# balise.net
KiCad netlist of a schematic drawn in EAGLE
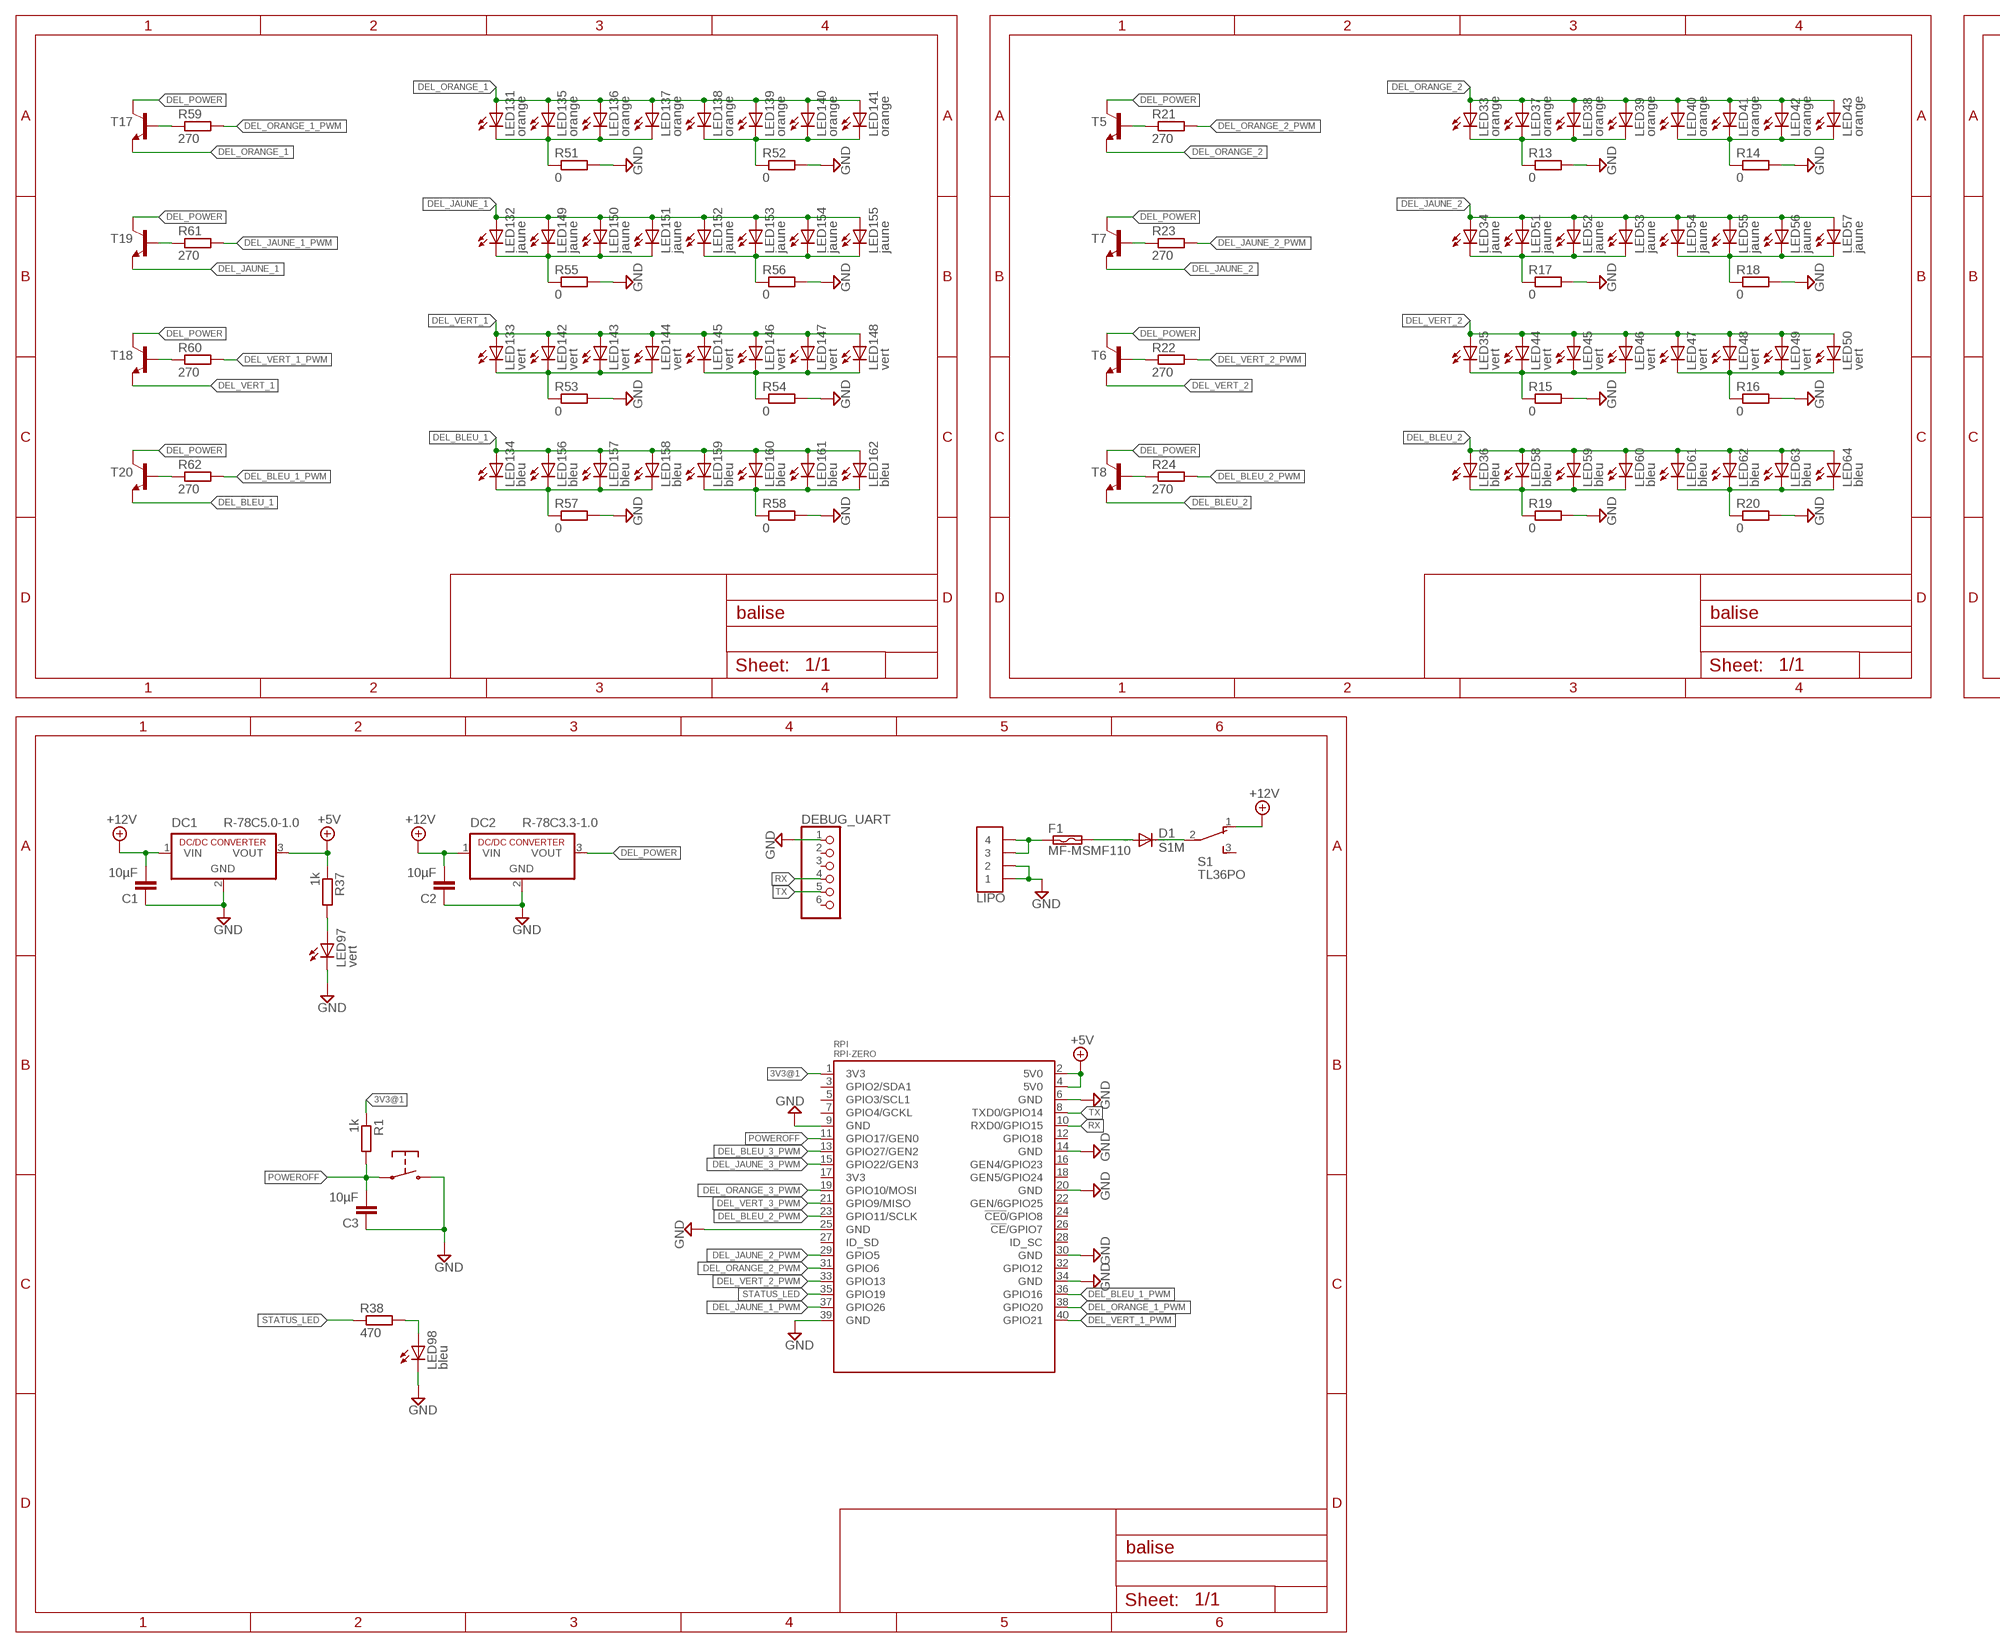
[diagram p0: schematic, sheet 1, part 1 of 2]
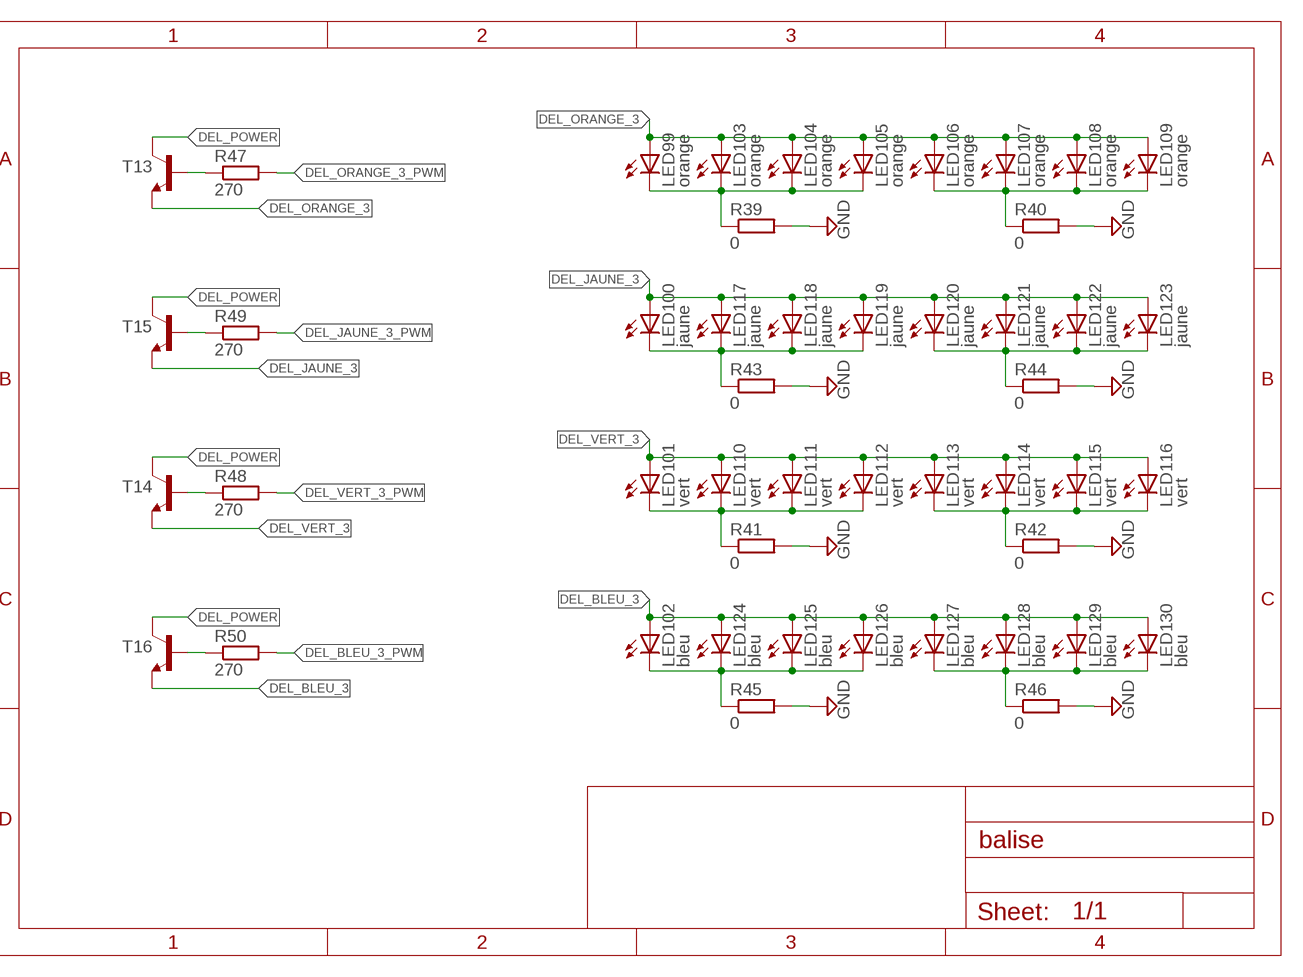
[diagram p1: schematic, sheet 1, part 2 of 2]

(export (version "E")
  (design (tool "Eeschema 10.0.6"))
  (components
    (comp (ref "C1")
      (value "10µF")
      (footprint "eagle-import:C0805")
      (libsource (lib "eagle-import") (part "C-EUC0805"))
    )
    (comp (ref "C2")
      (value "10µF")
      (footprint "eagle-import:C0805")
      (libsource (lib "eagle-import") (part "C-EUC0805"))
    )
    (comp (ref "C3")
      (value "10µF")
      (footprint "eagle-import:C0805")
      (libsource (lib "eagle-import") (part "C-EUC0805"))
    )
    (comp (ref "D1")
      (value "S1M")
      (footprint "eagle-import:SMA")
      (libsource (lib "eagle-import") (part "S1M"))
    )
    (comp (ref "DC1")
      (value "R-78C5.0-1.0")
      (footprint "eagle-import:SIP3")
      (libsource (lib "eagle-import") (part "R-78C-1.05.0"))
    )
    (comp (ref "DC2")
      (value "R-78C3.3-1.0")
      (footprint "eagle-import:SIP3")
      (libsource (lib "eagle-import") (part "R-78C-1.03.3"))
    )
    (comp (ref "DEBUG_UART")
      (value "PINHD-1X6")
      (footprint "eagle-import:1X06")
      (libsource (lib "eagle-import") (part "PINHD-1X6"))
    )
    (comp (ref "F1")
      (value "MF-MSMF110")
      (footprint "eagle-import:MF-MSMF110")
      (libsource (lib "eagle-import") (part "MF-MSMF110"))
    )
    (comp (ref "LED33")
      (value "orange")
      (footprint "eagle-import:LED5MM")
      (libsource (lib "eagle-import") (part "LED5MM"))
    )
    (comp (ref "LED34")
      (value "jaune")
      (footprint "eagle-import:LED5MM")
      (libsource (lib "eagle-import") (part "LED5MM"))
    )
    (comp (ref "LED35")
      (value "vert")
      (footprint "eagle-import:LED5MM")
      (libsource (lib "eagle-import") (part "LED5MM"))
    )
    (comp (ref "LED36")
      (value "bleu")
      (footprint "eagle-import:LED5MM")
      (libsource (lib "eagle-import") (part "LED5MM"))
    )
    (comp (ref "LED37")
      (value "orange")
      (footprint "eagle-import:LED5MM")
      (libsource (lib "eagle-import") (part "LED5MM"))
    )
    (comp (ref "LED38")
      (value "orange")
      (footprint "eagle-import:LED5MM")
      (libsource (lib "eagle-import") (part "LED5MM"))
    )
    (comp (ref "LED39")
      (value "orange")
      (footprint "eagle-import:LED5MM")
      (libsource (lib "eagle-import") (part "LED5MM"))
    )
    (comp (ref "LED40")
      (value "orange")
      (footprint "eagle-import:LED5MM")
      (libsource (lib "eagle-import") (part "LED5MM"))
    )
    (comp (ref "LED41")
      (value "orange")
      (footprint "eagle-import:LED5MM")
      (libsource (lib "eagle-import") (part "LED5MM"))
    )
    (comp (ref "LED42")
      (value "orange")
      (footprint "eagle-import:LED5MM")
      (libsource (lib "eagle-import") (part "LED5MM"))
    )
    (comp (ref "LED43")
      (value "orange")
      (footprint "eagle-import:LED5MM")
      (libsource (lib "eagle-import") (part "LED5MM"))
    )
    (comp (ref "LED44")
      (value "vert")
      (footprint "eagle-import:LED5MM")
      (libsource (lib "eagle-import") (part "LED5MM"))
    )
    (comp (ref "LED45")
      (value "vert")
      (footprint "eagle-import:LED5MM")
      (libsource (lib "eagle-import") (part "LED5MM"))
    )
    (comp (ref "LED46")
      (value "vert")
      (footprint "eagle-import:LED5MM")
      (libsource (lib "eagle-import") (part "LED5MM"))
    )
    (comp (ref "LED47")
      (value "vert")
      (footprint "eagle-import:LED5MM")
      (libsource (lib "eagle-import") (part "LED5MM"))
    )
    (comp (ref "LED48")
      (value "vert")
      (footprint "eagle-import:LED5MM")
      (libsource (lib "eagle-import") (part "LED5MM"))
    )
    (comp (ref "LED49")
      (value "vert")
      (footprint "eagle-import:LED5MM")
      (libsource (lib "eagle-import") (part "LED5MM"))
    )
    (comp (ref "LED50")
      (value "vert")
      (footprint "eagle-import:LED5MM")
      (libsource (lib "eagle-import") (part "LED5MM"))
    )
    (comp (ref "LED51")
      (value "jaune")
      (footprint "eagle-import:LED5MM")
      (libsource (lib "eagle-import") (part "LED5MM"))
    )
    (comp (ref "LED52")
      (value "jaune")
      (footprint "eagle-import:LED5MM")
      (libsource (lib "eagle-import") (part "LED5MM"))
    )
    (comp (ref "LED53")
      (value "jaune")
      (footprint "eagle-import:LED5MM")
      (libsource (lib "eagle-import") (part "LED5MM"))
    )
    (comp (ref "LED54")
      (value "jaune")
      (footprint "eagle-import:LED5MM")
      (libsource (lib "eagle-import") (part "LED5MM"))
    )
    (comp (ref "LED55")
      (value "jaune")
      (footprint "eagle-import:LED5MM")
      (libsource (lib "eagle-import") (part "LED5MM"))
    )
    (comp (ref "LED56")
      (value "jaune")
      (footprint "eagle-import:LED5MM")
      (libsource (lib "eagle-import") (part "LED5MM"))
    )
    (comp (ref "LED57")
      (value "jaune")
      (footprint "eagle-import:LED5MM")
      (libsource (lib "eagle-import") (part "LED5MM"))
    )
    (comp (ref "LED58")
      (value "bleu")
      (footprint "eagle-import:LED5MM")
      (libsource (lib "eagle-import") (part "LED5MM"))
    )
    (comp (ref "LED59")
      (value "bleu")
      (footprint "eagle-import:LED5MM")
      (libsource (lib "eagle-import") (part "LED5MM"))
    )
    (comp (ref "LED60")
      (value "bleu")
      (footprint "eagle-import:LED5MM")
      (libsource (lib "eagle-import") (part "LED5MM"))
    )
    (comp (ref "LED61")
      (value "bleu")
      (footprint "eagle-import:LED5MM")
      (libsource (lib "eagle-import") (part "LED5MM"))
    )
    (comp (ref "LED62")
      (value "bleu")
      (footprint "eagle-import:LED5MM")
      (libsource (lib "eagle-import") (part "LED5MM"))
    )
    (comp (ref "LED63")
      (value "bleu")
      (footprint "eagle-import:LED5MM")
      (libsource (lib "eagle-import") (part "LED5MM"))
    )
    (comp (ref "LED64")
      (value "bleu")
      (footprint "eagle-import:LED5MM")
      (libsource (lib "eagle-import") (part "LED5MM"))
    )
    (comp (ref "LED97")
      (value "vert")
      (footprint "eagle-import:LED5MM")
      (libsource (lib "eagle-import") (part "LED5MM"))
    )
    (comp (ref "LED98")
      (value "bleu")
      (footprint "eagle-import:LED5MM")
      (libsource (lib "eagle-import") (part "LED5MM"))
    )
    (comp (ref "LED99")
      (value "orange")
      (footprint "eagle-import:LED5MM")
      (libsource (lib "eagle-import") (part "LED5MM"))
    )
    (comp (ref "LED100")
      (value "jaune")
      (footprint "eagle-import:LED5MM")
      (libsource (lib "eagle-import") (part "LED5MM"))
    )
    (comp (ref "LED101")
      (value "vert")
      (footprint "eagle-import:LED5MM")
      (libsource (lib "eagle-import") (part "LED5MM"))
    )
    (comp (ref "LED102")
      (value "bleu")
      (footprint "eagle-import:LED5MM")
      (libsource (lib "eagle-import") (part "LED5MM"))
    )
    (comp (ref "LED103")
      (value "orange")
      (footprint "eagle-import:LED5MM")
      (libsource (lib "eagle-import") (part "LED5MM"))
    )
    (comp (ref "LED104")
      (value "orange")
      (footprint "eagle-import:LED5MM")
      (libsource (lib "eagle-import") (part "LED5MM"))
    )
    (comp (ref "LED105")
      (value "orange")
      (footprint "eagle-import:LED5MM")
      (libsource (lib "eagle-import") (part "LED5MM"))
    )
    (comp (ref "LED106")
      (value "orange")
      (footprint "eagle-import:LED5MM")
      (libsource (lib "eagle-import") (part "LED5MM"))
    )
    (comp (ref "LED107")
      (value "orange")
      (footprint "eagle-import:LED5MM")
      (libsource (lib "eagle-import") (part "LED5MM"))
    )
    (comp (ref "LED108")
      (value "orange")
      (footprint "eagle-import:LED5MM")
      (libsource (lib "eagle-import") (part "LED5MM"))
    )
    (comp (ref "LED109")
      (value "orange")
      (footprint "eagle-import:LED5MM")
      (libsource (lib "eagle-import") (part "LED5MM"))
    )
    (comp (ref "LED110")
      (value "vert")
      (footprint "eagle-import:LED5MM")
      (libsource (lib "eagle-import") (part "LED5MM"))
    )
    (comp (ref "LED111")
      (value "vert")
      (footprint "eagle-import:LED5MM")
      (libsource (lib "eagle-import") (part "LED5MM"))
    )
    (comp (ref "LED112")
      (value "vert")
      (footprint "eagle-import:LED5MM")
      (libsource (lib "eagle-import") (part "LED5MM"))
    )
    (comp (ref "LED113")
      (value "vert")
      (footprint "eagle-import:LED5MM")
      (libsource (lib "eagle-import") (part "LED5MM"))
    )
    (comp (ref "LED114")
      (value "vert")
      (footprint "eagle-import:LED5MM")
      (libsource (lib "eagle-import") (part "LED5MM"))
    )
    (comp (ref "LED115")
      (value "vert")
      (footprint "eagle-import:LED5MM")
      (libsource (lib "eagle-import") (part "LED5MM"))
    )
    (comp (ref "LED116")
      (value "vert")
      (footprint "eagle-import:LED5MM")
      (libsource (lib "eagle-import") (part "LED5MM"))
    )
    (comp (ref "LED117")
      (value "jaune")
      (footprint "eagle-import:LED5MM")
      (libsource (lib "eagle-import") (part "LED5MM"))
    )
    (comp (ref "LED118")
      (value "jaune")
      (footprint "eagle-import:LED5MM")
      (libsource (lib "eagle-import") (part "LED5MM"))
    )
    (comp (ref "LED119")
      (value "jaune")
      (footprint "eagle-import:LED5MM")
      (libsource (lib "eagle-import") (part "LED5MM"))
    )
    (comp (ref "LED120")
      (value "jaune")
      (footprint "eagle-import:LED5MM")
      (libsource (lib "eagle-import") (part "LED5MM"))
    )
    (comp (ref "LED121")
      (value "jaune")
      (footprint "eagle-import:LED5MM")
      (libsource (lib "eagle-import") (part "LED5MM"))
    )
    (comp (ref "LED122")
      (value "jaune")
      (footprint "eagle-import:LED5MM")
      (libsource (lib "eagle-import") (part "LED5MM"))
    )
    (comp (ref "LED123")
      (value "jaune")
      (footprint "eagle-import:LED5MM")
      (libsource (lib "eagle-import") (part "LED5MM"))
    )
    (comp (ref "LED124")
      (value "bleu")
      (footprint "eagle-import:LED5MM")
      (libsource (lib "eagle-import") (part "LED5MM"))
    )
    (comp (ref "LED125")
      (value "bleu")
      (footprint "eagle-import:LED5MM")
      (libsource (lib "eagle-import") (part "LED5MM"))
    )
    (comp (ref "LED126")
      (value "bleu")
      (footprint "eagle-import:LED5MM")
      (libsource (lib "eagle-import") (part "LED5MM"))
    )
    (comp (ref "LED127")
      (value "bleu")
      (footprint "eagle-import:LED5MM")
      (libsource (lib "eagle-import") (part "LED5MM"))
    )
    (comp (ref "LED128")
      (value "bleu")
      (footprint "eagle-import:LED5MM")
      (libsource (lib "eagle-import") (part "LED5MM"))
    )
    (comp (ref "LED129")
      (value "bleu")
      (footprint "eagle-import:LED5MM")
      (libsource (lib "eagle-import") (part "LED5MM"))
    )
    (comp (ref "LED130")
      (value "bleu")
      (footprint "eagle-import:LED5MM")
      (libsource (lib "eagle-import") (part "LED5MM"))
    )
    (comp (ref "LED131")
      (value "orange")
      (footprint "eagle-import:LED5MM")
      (libsource (lib "eagle-import") (part "LED5MM"))
    )
    (comp (ref "LED132")
      (value "jaune")
      (footprint "eagle-import:LED5MM")
      (libsource (lib "eagle-import") (part "LED5MM"))
    )
    (comp (ref "LED133")
      (value "vert")
      (footprint "eagle-import:LED5MM")
      (libsource (lib "eagle-import") (part "LED5MM"))
    )
    (comp (ref "LED134")
      (value "bleu")
      (footprint "eagle-import:LED5MM")
      (libsource (lib "eagle-import") (part "LED5MM"))
    )
    (comp (ref "LED135")
      (value "orange")
      (footprint "eagle-import:LED5MM")
      (libsource (lib "eagle-import") (part "LED5MM"))
    )
    (comp (ref "LED136")
      (value "orange")
      (footprint "eagle-import:LED5MM")
      (libsource (lib "eagle-import") (part "LED5MM"))
    )
    (comp (ref "LED137")
      (value "orange")
      (footprint "eagle-import:LED5MM")
      (libsource (lib "eagle-import") (part "LED5MM"))
    )
    (comp (ref "LED138")
      (value "orange")
      (footprint "eagle-import:LED5MM")
      (libsource (lib "eagle-import") (part "LED5MM"))
    )
    (comp (ref "LED139")
      (value "orange")
      (footprint "eagle-import:LED5MM")
      (libsource (lib "eagle-import") (part "LED5MM"))
    )
    (comp (ref "LED140")
      (value "orange")
      (footprint "eagle-import:LED5MM")
      (libsource (lib "eagle-import") (part "LED5MM"))
    )
    (comp (ref "LED141")
      (value "orange")
      (footprint "eagle-import:LED5MM")
      (libsource (lib "eagle-import") (part "LED5MM"))
    )
    (comp (ref "LED142")
      (value "vert")
      (footprint "eagle-import:LED5MM")
      (libsource (lib "eagle-import") (part "LED5MM"))
    )
    (comp (ref "LED143")
      (value "vert")
      (footprint "eagle-import:LED5MM")
      (libsource (lib "eagle-import") (part "LED5MM"))
    )
    (comp (ref "LED144")
      (value "vert")
      (footprint "eagle-import:LED5MM")
      (libsource (lib "eagle-import") (part "LED5MM"))
    )
    (comp (ref "LED145")
      (value "vert")
      (footprint "eagle-import:LED5MM")
      (libsource (lib "eagle-import") (part "LED5MM"))
    )
    (comp (ref "LED146")
      (value "vert")
      (footprint "eagle-import:LED5MM")
      (libsource (lib "eagle-import") (part "LED5MM"))
    )
    (comp (ref "LED147")
      (value "vert")
      (footprint "eagle-import:LED5MM")
      (libsource (lib "eagle-import") (part "LED5MM"))
    )
    (comp (ref "LED148")
      (value "vert")
      (footprint "eagle-import:LED5MM")
      (libsource (lib "eagle-import") (part "LED5MM"))
    )
    (comp (ref "LED149")
      (value "jaune")
      (footprint "eagle-import:LED5MM")
      (libsource (lib "eagle-import") (part "LED5MM"))
    )
    (comp (ref "LED150")
      (value "jaune")
      (footprint "eagle-import:LED5MM")
      (libsource (lib "eagle-import") (part "LED5MM"))
    )
    (comp (ref "LED151")
      (value "jaune")
      (footprint "eagle-import:LED5MM")
      (libsource (lib "eagle-import") (part "LED5MM"))
    )
    (comp (ref "LED152")
      (value "jaune")
      (footprint "eagle-import:LED5MM")
      (libsource (lib "eagle-import") (part "LED5MM"))
    )
    (comp (ref "LED153")
      (value "jaune")
      (footprint "eagle-import:LED5MM")
      (libsource (lib "eagle-import") (part "LED5MM"))
    )
    (comp (ref "LED154")
      (value "jaune")
      (footprint "eagle-import:LED5MM")
      (libsource (lib "eagle-import") (part "LED5MM"))
    )
    (comp (ref "LED155")
      (value "jaune")
      (footprint "eagle-import:LED5MM")
      (libsource (lib "eagle-import") (part "LED5MM"))
    )
    (comp (ref "LED156")
      (value "bleu")
      (footprint "eagle-import:LED5MM")
      (libsource (lib "eagle-import") (part "LED5MM"))
    )
    (comp (ref "LED157")
      (value "bleu")
      (footprint "eagle-import:LED5MM")
      (libsource (lib "eagle-import") (part "LED5MM"))
    )
    (comp (ref "LED158")
      (value "bleu")
      (footprint "eagle-import:LED5MM")
      (libsource (lib "eagle-import") (part "LED5MM"))
    )
    (comp (ref "LED159")
      (value "bleu")
      (footprint "eagle-import:LED5MM")
      (libsource (lib "eagle-import") (part "LED5MM"))
    )
    (comp (ref "LED160")
      (value "bleu")
      (footprint "eagle-import:LED5MM")
      (libsource (lib "eagle-import") (part "LED5MM"))
    )
    (comp (ref "LED161")
      (value "bleu")
      (footprint "eagle-import:LED5MM")
      (libsource (lib "eagle-import") (part "LED5MM"))
    )
    (comp (ref "LED162")
      (value "bleu")
      (footprint "eagle-import:LED5MM")
      (libsource (lib "eagle-import") (part "LED5MM"))
    )
    (comp (ref "LIPO")
      (value "JST-04GH-V")
      (footprint "eagle-import:GH-04-V")
      (libsource (lib "eagle-import") (part "JST-04GH-V"))
    )
    (comp (ref "R1")
      (value "1k")
      (footprint "eagle-import:R0805")
      (libsource (lib "eagle-import") (part "R-EU_R0805"))
    )
    (comp (ref "R13")
      (value "0")
      (footprint "eagle-import:R0805")
      (libsource (lib "eagle-import") (part "R-EU_R0805"))
    )
    (comp (ref "R14")
      (value "0")
      (footprint "eagle-import:R0805")
      (libsource (lib "eagle-import") (part "R-EU_R0805"))
    )
    (comp (ref "R15")
      (value "0")
      (footprint "eagle-import:R0805")
      (libsource (lib "eagle-import") (part "R-EU_R0805"))
    )
    (comp (ref "R16")
      (value "0")
      (footprint "eagle-import:R0805")
      (libsource (lib "eagle-import") (part "R-EU_R0805"))
    )
    (comp (ref "R17")
      (value "0")
      (footprint "eagle-import:R0805")
      (libsource (lib "eagle-import") (part "R-EU_R0805"))
    )
    (comp (ref "R18")
      (value "0")
      (footprint "eagle-import:R0805")
      (libsource (lib "eagle-import") (part "R-EU_R0805"))
    )
    (comp (ref "R19")
      (value "0")
      (footprint "eagle-import:R0805")
      (libsource (lib "eagle-import") (part "R-EU_R0805"))
    )
    (comp (ref "R20")
      (value "0")
      (footprint "eagle-import:R0805")
      (libsource (lib "eagle-import") (part "R-EU_R0805"))
    )
    (comp (ref "R21")
      (value "270")
      (footprint "eagle-import:R0805")
      (libsource (lib "eagle-import") (part "R-EU_R0805"))
    )
    (comp (ref "R22")
      (value "270")
      (footprint "eagle-import:R0805")
      (libsource (lib "eagle-import") (part "R-EU_R0805"))
    )
    (comp (ref "R23")
      (value "270")
      (footprint "eagle-import:R0805")
      (libsource (lib "eagle-import") (part "R-EU_R0805"))
    )
    (comp (ref "R24")
      (value "270")
      (footprint "eagle-import:R0805")
      (libsource (lib "eagle-import") (part "R-EU_R0805"))
    )
    (comp (ref "R37")
      (value "1k")
      (footprint "eagle-import:R0805")
      (libsource (lib "eagle-import") (part "R-EU_R0805"))
    )
    (comp (ref "R38")
      (value "470")
      (footprint "eagle-import:R0805")
      (libsource (lib "eagle-import") (part "R-EU_R0805"))
    )
    (comp (ref "R39")
      (value "0")
      (footprint "eagle-import:R0805")
      (libsource (lib "eagle-import") (part "R-EU_R0805"))
    )
    (comp (ref "R40")
      (value "0")
      (footprint "eagle-import:R0805")
      (libsource (lib "eagle-import") (part "R-EU_R0805"))
    )
    (comp (ref "R41")
      (value "0")
      (footprint "eagle-import:R0805")
      (libsource (lib "eagle-import") (part "R-EU_R0805"))
    )
    (comp (ref "R42")
      (value "0")
      (footprint "eagle-import:R0805")
      (libsource (lib "eagle-import") (part "R-EU_R0805"))
    )
    (comp (ref "R43")
      (value "0")
      (footprint "eagle-import:R0805")
      (libsource (lib "eagle-import") (part "R-EU_R0805"))
    )
    (comp (ref "R44")
      (value "0")
      (footprint "eagle-import:R0805")
      (libsource (lib "eagle-import") (part "R-EU_R0805"))
    )
    (comp (ref "R45")
      (value "0")
      (footprint "eagle-import:R0805")
      (libsource (lib "eagle-import") (part "R-EU_R0805"))
    )
    (comp (ref "R46")
      (value "0")
      (footprint "eagle-import:R0805")
      (libsource (lib "eagle-import") (part "R-EU_R0805"))
    )
    (comp (ref "R47")
      (value "270")
      (footprint "eagle-import:R0805")
      (libsource (lib "eagle-import") (part "R-EU_R0805"))
    )
    (comp (ref "R48")
      (value "270")
      (footprint "eagle-import:R0805")
      (libsource (lib "eagle-import") (part "R-EU_R0805"))
    )
    (comp (ref "R49")
      (value "270")
      (footprint "eagle-import:R0805")
      (libsource (lib "eagle-import") (part "R-EU_R0805"))
    )
    (comp (ref "R50")
      (value "270")
      (footprint "eagle-import:R0805")
      (libsource (lib "eagle-import") (part "R-EU_R0805"))
    )
    (comp (ref "R51")
      (value "0")
      (footprint "eagle-import:R0805")
      (libsource (lib "eagle-import") (part "R-EU_R0805"))
    )
    (comp (ref "R52")
      (value "0")
      (footprint "eagle-import:R0805")
      (libsource (lib "eagle-import") (part "R-EU_R0805"))
    )
    (comp (ref "R53")
      (value "0")
      (footprint "eagle-import:R0805")
      (libsource (lib "eagle-import") (part "R-EU_R0805"))
    )
    (comp (ref "R54")
      (value "0")
      (footprint "eagle-import:R0805")
      (libsource (lib "eagle-import") (part "R-EU_R0805"))
    )
    (comp (ref "R55")
      (value "0")
      (footprint "eagle-import:R0805")
      (libsource (lib "eagle-import") (part "R-EU_R0805"))
    )
    (comp (ref "R56")
      (value "0")
      (footprint "eagle-import:R0805")
      (libsource (lib "eagle-import") (part "R-EU_R0805"))
    )
    (comp (ref "R57")
      (value "0")
      (footprint "eagle-import:R0805")
      (libsource (lib "eagle-import") (part "R-EU_R0805"))
    )
    (comp (ref "R58")
      (value "0")
      (footprint "eagle-import:R0805")
      (libsource (lib "eagle-import") (part "R-EU_R0805"))
    )
    (comp (ref "R59")
      (value "270")
      (footprint "eagle-import:R0805")
      (libsource (lib "eagle-import") (part "R-EU_R0805"))
    )
    (comp (ref "R60")
      (value "270")
      (footprint "eagle-import:R0805")
      (libsource (lib "eagle-import") (part "R-EU_R0805"))
    )
    (comp (ref "R61")
      (value "270")
      (footprint "eagle-import:R0805")
      (libsource (lib "eagle-import") (part "R-EU_R0805"))
    )
    (comp (ref "R62")
      (value "270")
      (footprint "eagle-import:R0805")
      (libsource (lib "eagle-import") (part "R-EU_R0805"))
    )
    (comp (ref "RPI")
      (value "RPI-ZERO")
      (footprint "eagle-import:RASPBERRYPI_BASTELSTUBE_V13_RASPI_BOARD_B+_FULL")
      (libsource (lib "eagle-import") (part "RPI-ZERO"))
    )
    (comp (ref "S1")
      (value "TL36PO")
      (footprint "eagle-import:TL3XPO")
      (libsource (lib "eagle-import") (part "TL36PO"))
    )
    (comp (ref "T5")
      (value "BC817-16-NPN-SOT23-BEC")
      (footprint "eagle-import:SOT23-BEC")
      (libsource (lib "eagle-import") (part "-NPN-SOT23-BECBC817-16"))
    )
    (comp (ref "T6")
      (value "BC817-16-NPN-SOT23-BEC")
      (footprint "eagle-import:SOT23-BEC")
      (libsource (lib "eagle-import") (part "-NPN-SOT23-BECBC817-16"))
    )
    (comp (ref "T7")
      (value "BC817-16-NPN-SOT23-BEC")
      (footprint "eagle-import:SOT23-BEC")
      (libsource (lib "eagle-import") (part "-NPN-SOT23-BECBC817-16"))
    )
    (comp (ref "T8")
      (value "BC817-16-NPN-SOT23-BEC")
      (footprint "eagle-import:SOT23-BEC")
      (libsource (lib "eagle-import") (part "-NPN-SOT23-BECBC817-16"))
    )
    (comp (ref "T13")
      (value "BC817-16-NPN-SOT23-BEC")
      (footprint "eagle-import:SOT23-BEC")
      (libsource (lib "eagle-import") (part "-NPN-SOT23-BECBC817-16"))
    )
    (comp (ref "T14")
      (value "BC817-16-NPN-SOT23-BEC")
      (footprint "eagle-import:SOT23-BEC")
      (libsource (lib "eagle-import") (part "-NPN-SOT23-BECBC817-16"))
    )
    (comp (ref "T15")
      (value "BC817-16-NPN-SOT23-BEC")
      (footprint "eagle-import:SOT23-BEC")
      (libsource (lib "eagle-import") (part "-NPN-SOT23-BECBC817-16"))
    )
    (comp (ref "T16")
      (value "BC817-16-NPN-SOT23-BEC")
      (footprint "eagle-import:SOT23-BEC")
      (libsource (lib "eagle-import") (part "-NPN-SOT23-BECBC817-16"))
    )
    (comp (ref "T17")
      (value "BC817-16-NPN-SOT23-BEC")
      (footprint "eagle-import:SOT23-BEC")
      (libsource (lib "eagle-import") (part "-NPN-SOT23-BECBC817-16"))
    )
    (comp (ref "T18")
      (value "BC817-16-NPN-SOT23-BEC")
      (footprint "eagle-import:SOT23-BEC")
      (libsource (lib "eagle-import") (part "-NPN-SOT23-BECBC817-16"))
    )
    (comp (ref "T19")
      (value "BC817-16-NPN-SOT23-BEC")
      (footprint "eagle-import:SOT23-BEC")
      (libsource (lib "eagle-import") (part "-NPN-SOT23-BECBC817-16"))
    )
    (comp (ref "T20")
      (value "BC817-16-NPN-SOT23-BEC")
      (footprint "eagle-import:SOT23-BEC")
      (libsource (lib "eagle-import") (part "-NPN-SOT23-BECBC817-16"))
    )
    (comp (ref "U$1")
      (value "PUSH-BUTTON")
      (footprint "eagle-import:PUSH-BUTTON")
      (libsource (lib "eagle-import") (part "PUSH-BUTTON"))
    )
  )
  (nets
    (net (code "1") (name "+5V") (class "Default")
      (node (ref "DC1") (pin "3") (pinfunction "VOUT_3") (pintype "passive"))
      (node (ref "R37") (pin "1") (pinfunction "1_1") (pintype "passive"))
      (node (ref "RPI") (pin "2") (pinfunction "5V0_2") (pintype "power_in"))
      (node (ref "RPI") (pin "4") (pinfunction "5V0_4") (pintype "power_in"))
    )
    (net (code "2") (name "+12V") (class "Default")
      (node (ref "C1") (pin "2") (pinfunction "2_2") (pintype "passive"))
      (node (ref "C2") (pin "2") (pinfunction "2_2") (pintype "passive"))
      (node (ref "DC1") (pin "1") (pinfunction "VIN_1") (pintype "passive"))
      (node (ref "DC2") (pin "1") (pinfunction "VIN_1") (pintype "passive"))
      (node (ref "S1") (pin "1") (pinfunction "O_1") (pintype "passive"))
    )
    (net (code "3") (name "/3V3") (class "Default")
      (node (ref "RPI") (pin "17") (pinfunction "3V3_17") (pintype "power_in"))
    )
    (net (code "4") (name "3V3@1") (class "Default")
      (node (ref "R1") (pin "1") (pinfunction "1_1") (pintype "passive"))
      (node (ref "RPI") (pin "1") (pinfunction "3V3_1") (pintype "power_in"))
    )
    (net (code "5") (name "DEL_BLEU_1") (class "Default")
      (node (ref "LED134") (pin "A") (pinfunction "A_A") (pintype "passive"))
      (node (ref "LED156") (pin "A") (pinfunction "A_A") (pintype "passive"))
      (node (ref "LED157") (pin "A") (pinfunction "A_A") (pintype "passive"))
      (node (ref "LED158") (pin "A") (pinfunction "A_A") (pintype "passive"))
      (node (ref "LED159") (pin "A") (pinfunction "A_A") (pintype "passive"))
      (node (ref "LED160") (pin "A") (pinfunction "A_A") (pintype "passive"))
      (node (ref "LED161") (pin "A") (pinfunction "A_A") (pintype "passive"))
      (node (ref "LED162") (pin "A") (pinfunction "A_A") (pintype "passive"))
      (node (ref "T20") (pin "E") (pinfunction "E_E") (pintype "passive"))
    )
    (net (code "6") (name "DEL_BLEU_1_PWM") (class "Default")
      (node (ref "R62") (pin "2") (pinfunction "2_2") (pintype "passive"))
      (node (ref "RPI") (pin "36") (pinfunction "GPIO16_36") (pintype "bidirectional"))
    )
    (net (code "7") (name "DEL_BLEU_2") (class "Default")
      (node (ref "LED36") (pin "A") (pinfunction "A_A") (pintype "passive"))
      (node (ref "LED58") (pin "A") (pinfunction "A_A") (pintype "passive"))
      (node (ref "LED59") (pin "A") (pinfunction "A_A") (pintype "passive"))
      (node (ref "LED60") (pin "A") (pinfunction "A_A") (pintype "passive"))
      (node (ref "LED61") (pin "A") (pinfunction "A_A") (pintype "passive"))
      (node (ref "LED62") (pin "A") (pinfunction "A_A") (pintype "passive"))
      (node (ref "LED63") (pin "A") (pinfunction "A_A") (pintype "passive"))
      (node (ref "LED64") (pin "A") (pinfunction "A_A") (pintype "passive"))
      (node (ref "T8") (pin "E") (pinfunction "E_E") (pintype "passive"))
    )
    (net (code "8") (name "DEL_BLEU_2_PWM") (class "Default")
      (node (ref "R24") (pin "2") (pinfunction "2_2") (pintype "passive"))
      (node (ref "RPI") (pin "23") (pinfunction "GPIO11/SCLK_23") (pintype "bidirectional"))
    )
    (net (code "9") (name "DEL_BLEU_3") (class "Default")
      (node (ref "LED102") (pin "A") (pinfunction "A_A") (pintype "passive"))
      (node (ref "LED124") (pin "A") (pinfunction "A_A") (pintype "passive"))
      (node (ref "LED125") (pin "A") (pinfunction "A_A") (pintype "passive"))
      (node (ref "LED126") (pin "A") (pinfunction "A_A") (pintype "passive"))
      (node (ref "LED127") (pin "A") (pinfunction "A_A") (pintype "passive"))
      (node (ref "LED128") (pin "A") (pinfunction "A_A") (pintype "passive"))
      (node (ref "LED129") (pin "A") (pinfunction "A_A") (pintype "passive"))
      (node (ref "LED130") (pin "A") (pinfunction "A_A") (pintype "passive"))
      (node (ref "T16") (pin "E") (pinfunction "E_E") (pintype "passive"))
    )
    (net (code "10") (name "DEL_BLEU_3_PWM") (class "Default")
      (node (ref "R50") (pin "2") (pinfunction "2_2") (pintype "passive"))
      (node (ref "RPI") (pin "13") (pinfunction "GPIO27/GEN2_13") (pintype "bidirectional"))
    )
    (net (code "11") (name "DEL_JAUNE_1") (class "Default")
      (node (ref "LED132") (pin "A") (pinfunction "A_A") (pintype "passive"))
      (node (ref "LED149") (pin "A") (pinfunction "A_A") (pintype "passive"))
      (node (ref "LED150") (pin "A") (pinfunction "A_A") (pintype "passive"))
      (node (ref "LED151") (pin "A") (pinfunction "A_A") (pintype "passive"))
      (node (ref "LED152") (pin "A") (pinfunction "A_A") (pintype "passive"))
      (node (ref "LED153") (pin "A") (pinfunction "A_A") (pintype "passive"))
      (node (ref "LED154") (pin "A") (pinfunction "A_A") (pintype "passive"))
      (node (ref "LED155") (pin "A") (pinfunction "A_A") (pintype "passive"))
      (node (ref "T19") (pin "E") (pinfunction "E_E") (pintype "passive"))
    )
    (net (code "12") (name "DEL_JAUNE_1_PWM") (class "Default")
      (node (ref "R61") (pin "2") (pinfunction "2_2") (pintype "passive"))
      (node (ref "RPI") (pin "37") (pinfunction "GPIO26_37") (pintype "bidirectional"))
    )
    (net (code "13") (name "DEL_JAUNE_2") (class "Default")
      (node (ref "LED34") (pin "A") (pinfunction "A_A") (pintype "passive"))
      (node (ref "LED51") (pin "A") (pinfunction "A_A") (pintype "passive"))
      (node (ref "LED52") (pin "A") (pinfunction "A_A") (pintype "passive"))
      (node (ref "LED53") (pin "A") (pinfunction "A_A") (pintype "passive"))
      (node (ref "LED54") (pin "A") (pinfunction "A_A") (pintype "passive"))
      (node (ref "LED55") (pin "A") (pinfunction "A_A") (pintype "passive"))
      (node (ref "LED56") (pin "A") (pinfunction "A_A") (pintype "passive"))
      (node (ref "LED57") (pin "A") (pinfunction "A_A") (pintype "passive"))
      (node (ref "T7") (pin "E") (pinfunction "E_E") (pintype "passive"))
    )
    (net (code "14") (name "DEL_JAUNE_2_PWM") (class "Default")
      (node (ref "R23") (pin "2") (pinfunction "2_2") (pintype "passive"))
      (node (ref "RPI") (pin "29") (pinfunction "GPIO5_29") (pintype "bidirectional"))
    )
    (net (code "15") (name "DEL_JAUNE_3") (class "Default")
      (node (ref "LED100") (pin "A") (pinfunction "A_A") (pintype "passive"))
      (node (ref "LED117") (pin "A") (pinfunction "A_A") (pintype "passive"))
      (node (ref "LED118") (pin "A") (pinfunction "A_A") (pintype "passive"))
      (node (ref "LED119") (pin "A") (pinfunction "A_A") (pintype "passive"))
      (node (ref "LED120") (pin "A") (pinfunction "A_A") (pintype "passive"))
      (node (ref "LED121") (pin "A") (pinfunction "A_A") (pintype "passive"))
      (node (ref "LED122") (pin "A") (pinfunction "A_A") (pintype "passive"))
      (node (ref "LED123") (pin "A") (pinfunction "A_A") (pintype "passive"))
      (node (ref "T15") (pin "E") (pinfunction "E_E") (pintype "passive"))
    )
    (net (code "16") (name "DEL_JAUNE_3_PWM") (class "Default")
      (node (ref "R49") (pin "2") (pinfunction "2_2") (pintype "passive"))
      (node (ref "RPI") (pin "15") (pinfunction "GPIO22/GEN3_15") (pintype "bidirectional"))
    )
    (net (code "17") (name "DEL_ORANGE_1") (class "Default")
      (node (ref "LED131") (pin "A") (pinfunction "A_A") (pintype "passive"))
      (node (ref "LED135") (pin "A") (pinfunction "A_A") (pintype "passive"))
      (node (ref "LED136") (pin "A") (pinfunction "A_A") (pintype "passive"))
      (node (ref "LED137") (pin "A") (pinfunction "A_A") (pintype "passive"))
      (node (ref "LED138") (pin "A") (pinfunction "A_A") (pintype "passive"))
      (node (ref "LED139") (pin "A") (pinfunction "A_A") (pintype "passive"))
      (node (ref "LED140") (pin "A") (pinfunction "A_A") (pintype "passive"))
      (node (ref "LED141") (pin "A") (pinfunction "A_A") (pintype "passive"))
      (node (ref "T17") (pin "E") (pinfunction "E_E") (pintype "passive"))
    )
    (net (code "18") (name "DEL_ORANGE_1_PWM") (class "Default")
      (node (ref "R59") (pin "2") (pinfunction "2_2") (pintype "passive"))
      (node (ref "RPI") (pin "38") (pinfunction "GPIO20_38") (pintype "bidirectional"))
    )
    (net (code "19") (name "DEL_ORANGE_2") (class "Default")
      (node (ref "LED33") (pin "A") (pinfunction "A_A") (pintype "passive"))
      (node (ref "LED37") (pin "A") (pinfunction "A_A") (pintype "passive"))
      (node (ref "LED38") (pin "A") (pinfunction "A_A") (pintype "passive"))
      (node (ref "LED39") (pin "A") (pinfunction "A_A") (pintype "passive"))
      (node (ref "LED40") (pin "A") (pinfunction "A_A") (pintype "passive"))
      (node (ref "LED41") (pin "A") (pinfunction "A_A") (pintype "passive"))
      (node (ref "LED42") (pin "A") (pinfunction "A_A") (pintype "passive"))
      (node (ref "LED43") (pin "A") (pinfunction "A_A") (pintype "passive"))
      (node (ref "T5") (pin "E") (pinfunction "E_E") (pintype "passive"))
    )
    (net (code "20") (name "DEL_ORANGE_2_PWM") (class "Default")
      (node (ref "R21") (pin "2") (pinfunction "2_2") (pintype "passive"))
      (node (ref "RPI") (pin "31") (pinfunction "GPIO6_31") (pintype "bidirectional"))
    )
    (net (code "21") (name "DEL_ORANGE_3") (class "Default")
      (node (ref "LED103") (pin "A") (pinfunction "A_A") (pintype "passive"))
      (node (ref "LED104") (pin "A") (pinfunction "A_A") (pintype "passive"))
      (node (ref "LED105") (pin "A") (pinfunction "A_A") (pintype "passive"))
      (node (ref "LED106") (pin "A") (pinfunction "A_A") (pintype "passive"))
      (node (ref "LED107") (pin "A") (pinfunction "A_A") (pintype "passive"))
      (node (ref "LED108") (pin "A") (pinfunction "A_A") (pintype "passive"))
      (node (ref "LED109") (pin "A") (pinfunction "A_A") (pintype "passive"))
      (node (ref "LED99") (pin "A") (pinfunction "A_A") (pintype "passive"))
      (node (ref "T13") (pin "E") (pinfunction "E_E") (pintype "passive"))
    )
    (net (code "22") (name "DEL_ORANGE_3_PWM") (class "Default")
      (node (ref "R47") (pin "2") (pinfunction "2_2") (pintype "passive"))
      (node (ref "RPI") (pin "19") (pinfunction "GPIO10/MOSI_19") (pintype "bidirectional"))
    )
    (net (code "23") (name "DEL_POWER") (class "Default")
      (node (ref "DC2") (pin "3") (pinfunction "VOUT_3") (pintype "passive"))
      (node (ref "T13") (pin "C") (pinfunction "C_C") (pintype "passive"))
      (node (ref "T14") (pin "C") (pinfunction "C_C") (pintype "passive"))
      (node (ref "T15") (pin "C") (pinfunction "C_C") (pintype "passive"))
      (node (ref "T16") (pin "C") (pinfunction "C_C") (pintype "passive"))
      (node (ref "T17") (pin "C") (pinfunction "C_C") (pintype "passive"))
      (node (ref "T18") (pin "C") (pinfunction "C_C") (pintype "passive"))
      (node (ref "T19") (pin "C") (pinfunction "C_C") (pintype "passive"))
      (node (ref "T20") (pin "C") (pinfunction "C_C") (pintype "passive"))
      (node (ref "T5") (pin "C") (pinfunction "C_C") (pintype "passive"))
      (node (ref "T6") (pin "C") (pinfunction "C_C") (pintype "passive"))
      (node (ref "T7") (pin "C") (pinfunction "C_C") (pintype "passive"))
      (node (ref "T8") (pin "C") (pinfunction "C_C") (pintype "passive"))
    )
    (net (code "24") (name "DEL_VERT_1") (class "Default")
      (node (ref "LED133") (pin "A") (pinfunction "A_A") (pintype "passive"))
      (node (ref "LED142") (pin "A") (pinfunction "A_A") (pintype "passive"))
      (node (ref "LED143") (pin "A") (pinfunction "A_A") (pintype "passive"))
      (node (ref "LED144") (pin "A") (pinfunction "A_A") (pintype "passive"))
      (node (ref "LED145") (pin "A") (pinfunction "A_A") (pintype "passive"))
      (node (ref "LED146") (pin "A") (pinfunction "A_A") (pintype "passive"))
      (node (ref "LED147") (pin "A") (pinfunction "A_A") (pintype "passive"))
      (node (ref "LED148") (pin "A") (pinfunction "A_A") (pintype "passive"))
      (node (ref "T18") (pin "E") (pinfunction "E_E") (pintype "passive"))
    )
    (net (code "25") (name "DEL_VERT_1_PWM") (class "Default")
      (node (ref "R60") (pin "2") (pinfunction "2_2") (pintype "passive"))
      (node (ref "RPI") (pin "40") (pinfunction "GPIO21_40") (pintype "bidirectional"))
    )
    (net (code "26") (name "DEL_VERT_2") (class "Default")
      (node (ref "LED35") (pin "A") (pinfunction "A_A") (pintype "passive"))
      (node (ref "LED44") (pin "A") (pinfunction "A_A") (pintype "passive"))
      (node (ref "LED45") (pin "A") (pinfunction "A_A") (pintype "passive"))
      (node (ref "LED46") (pin "A") (pinfunction "A_A") (pintype "passive"))
      (node (ref "LED47") (pin "A") (pinfunction "A_A") (pintype "passive"))
      (node (ref "LED48") (pin "A") (pinfunction "A_A") (pintype "passive"))
      (node (ref "LED49") (pin "A") (pinfunction "A_A") (pintype "passive"))
      (node (ref "LED50") (pin "A") (pinfunction "A_A") (pintype "passive"))
      (node (ref "T6") (pin "E") (pinfunction "E_E") (pintype "passive"))
    )
    (net (code "27") (name "DEL_VERT_2_PWM") (class "Default")
      (node (ref "R22") (pin "2") (pinfunction "2_2") (pintype "passive"))
      (node (ref "RPI") (pin "33") (pinfunction "GPIO13_33") (pintype "bidirectional"))
    )
    (net (code "28") (name "DEL_VERT_3") (class "Default")
      (node (ref "LED101") (pin "A") (pinfunction "A_A") (pintype "passive"))
      (node (ref "LED110") (pin "A") (pinfunction "A_A") (pintype "passive"))
      (node (ref "LED111") (pin "A") (pinfunction "A_A") (pintype "passive"))
      (node (ref "LED112") (pin "A") (pinfunction "A_A") (pintype "passive"))
      (node (ref "LED113") (pin "A") (pinfunction "A_A") (pintype "passive"))
      (node (ref "LED114") (pin "A") (pinfunction "A_A") (pintype "passive"))
      (node (ref "LED115") (pin "A") (pinfunction "A_A") (pintype "passive"))
      (node (ref "LED116") (pin "A") (pinfunction "A_A") (pintype "passive"))
      (node (ref "T14") (pin "E") (pinfunction "E_E") (pintype "passive"))
    )
    (net (code "29") (name "DEL_VERT_3_PWM") (class "Default")
      (node (ref "R48") (pin "2") (pinfunction "2_2") (pintype "passive"))
      (node (ref "RPI") (pin "21") (pinfunction "GPIO9/MISO_21") (pintype "bidirectional"))
    )
    (net (code "30") (name "GND") (class "Default")
      (node (ref "C1") (pin "1") (pinfunction "1_1") (pintype "passive"))
      (node (ref "C2") (pin "1") (pinfunction "1_1") (pintype "passive"))
      (node (ref "C3") (pin "1") (pinfunction "1_1") (pintype "passive"))
      (node (ref "DC1") (pin "2") (pinfunction "GND_2") (pintype "passive"))
      (node (ref "DC2") (pin "2") (pinfunction "GND_2") (pintype "passive"))
      (node (ref "DEBUG_UART") (pin "1") (pinfunction "1_1") (pintype "passive"))
      (node (ref "LED97") (pin "K") (pinfunction "C_K") (pintype "passive"))
      (node (ref "LED98") (pin "K") (pinfunction "C_K") (pintype "passive"))
      (node (ref "LIPO") (pin "1") (pinfunction "1_1") (pintype "bidirectional"))
      (node (ref "LIPO") (pin "2") (pinfunction "2_2") (pintype "bidirectional"))
      (node (ref "R13") (pin "2") (pinfunction "2_2") (pintype "passive"))
      (node (ref "R14") (pin "2") (pinfunction "2_2") (pintype "passive"))
      (node (ref "R15") (pin "2") (pinfunction "2_2") (pintype "passive"))
      (node (ref "R16") (pin "2") (pinfunction "2_2") (pintype "passive"))
      (node (ref "R17") (pin "2") (pinfunction "2_2") (pintype "passive"))
      (node (ref "R18") (pin "2") (pinfunction "2_2") (pintype "passive"))
      (node (ref "R19") (pin "2") (pinfunction "2_2") (pintype "passive"))
      (node (ref "R20") (pin "2") (pinfunction "2_2") (pintype "passive"))
      (node (ref "R39") (pin "2") (pinfunction "2_2") (pintype "passive"))
      (node (ref "R40") (pin "2") (pinfunction "2_2") (pintype "passive"))
      (node (ref "R41") (pin "2") (pinfunction "2_2") (pintype "passive"))
      (node (ref "R42") (pin "2") (pinfunction "2_2") (pintype "passive"))
      (node (ref "R43") (pin "2") (pinfunction "2_2") (pintype "passive"))
      (node (ref "R44") (pin "2") (pinfunction "2_2") (pintype "passive"))
      (node (ref "R45") (pin "2") (pinfunction "2_2") (pintype "passive"))
      (node (ref "R46") (pin "2") (pinfunction "2_2") (pintype "passive"))
      (node (ref "R51") (pin "2") (pinfunction "2_2") (pintype "passive"))
      (node (ref "R52") (pin "2") (pinfunction "2_2") (pintype "passive"))
      (node (ref "R53") (pin "2") (pinfunction "2_2") (pintype "passive"))
      (node (ref "R54") (pin "2") (pinfunction "2_2") (pintype "passive"))
      (node (ref "R55") (pin "2") (pinfunction "2_2") (pintype "passive"))
      (node (ref "R56") (pin "2") (pinfunction "2_2") (pintype "passive"))
      (node (ref "R57") (pin "2") (pinfunction "2_2") (pintype "passive"))
      (node (ref "R58") (pin "2") (pinfunction "2_2") (pintype "passive"))
      (node (ref "RPI") (pin "14") (pinfunction "GND_14") (pintype "power_in"))
      (node (ref "RPI") (pin "20") (pinfunction "GND_20") (pintype "power_in"))
      (node (ref "RPI") (pin "25") (pinfunction "GND_25") (pintype "power_in"))
      (node (ref "RPI") (pin "30") (pinfunction "GND_30") (pintype "power_in"))
      (node (ref "RPI") (pin "34") (pinfunction "GND_34") (pintype "power_in"))
      (node (ref "RPI") (pin "39") (pinfunction "GND_39") (pintype "power_in"))
      (node (ref "RPI") (pin "6") (pinfunction "GND_6") (pintype "power_in"))
      (node (ref "RPI") (pin "9") (pinfunction "GND_9") (pintype "power_in"))
      (node (ref "U$1") (pin "3") (pinfunction "P$2_3") (pintype "bidirectional"))
      (node (ref "U$1") (pin "4") (pinfunction "P$2_4") (pintype "bidirectional"))
    )
    (net (code "31") (name "Net-(D1-PadA)") (class "Default")
      (node (ref "D1") (pin "A") (pinfunction "A_A") (pintype "passive"))
      (node (ref "F1") (pin "2") (pinfunction "2_2") (pintype "passive"))
    )
    (net (code "32") (name "Net-(F1-Pad1)") (class "Default")
      (node (ref "F1") (pin "1") (pinfunction "1_1") (pintype "passive"))
      (node (ref "LIPO") (pin "3") (pinfunction "3_3") (pintype "bidirectional"))
      (node (ref "LIPO") (pin "4") (pinfunction "4_4") (pintype "bidirectional"))
    )
    (net (code "33") (name "Net-(LED33-C)") (class "Default")
      (node (ref "LED33") (pin "K") (pinfunction "C_K") (pintype "passive"))
      (node (ref "LED37") (pin "K") (pinfunction "C_K") (pintype "passive"))
      (node (ref "LED38") (pin "K") (pinfunction "C_K") (pintype "passive"))
      (node (ref "LED39") (pin "K") (pinfunction "C_K") (pintype "passive"))
      (node (ref "R13") (pin "1") (pinfunction "1_1") (pintype "passive"))
    )
    (net (code "34") (name "Net-(LED34-C)") (class "Default")
      (node (ref "LED34") (pin "K") (pinfunction "C_K") (pintype "passive"))
      (node (ref "LED51") (pin "K") (pinfunction "C_K") (pintype "passive"))
      (node (ref "LED52") (pin "K") (pinfunction "C_K") (pintype "passive"))
      (node (ref "LED53") (pin "K") (pinfunction "C_K") (pintype "passive"))
      (node (ref "R17") (pin "1") (pinfunction "1_1") (pintype "passive"))
    )
    (net (code "35") (name "Net-(LED35-C)") (class "Default")
      (node (ref "LED35") (pin "K") (pinfunction "C_K") (pintype "passive"))
      (node (ref "LED44") (pin "K") (pinfunction "C_K") (pintype "passive"))
      (node (ref "LED45") (pin "K") (pinfunction "C_K") (pintype "passive"))
      (node (ref "LED46") (pin "K") (pinfunction "C_K") (pintype "passive"))
      (node (ref "R15") (pin "1") (pinfunction "1_1") (pintype "passive"))
    )
    (net (code "36") (name "Net-(LED36-C)") (class "Default")
      (node (ref "LED36") (pin "K") (pinfunction "C_K") (pintype "passive"))
      (node (ref "LED58") (pin "K") (pinfunction "C_K") (pintype "passive"))
      (node (ref "LED59") (pin "K") (pinfunction "C_K") (pintype "passive"))
      (node (ref "LED60") (pin "K") (pinfunction "C_K") (pintype "passive"))
      (node (ref "R19") (pin "1") (pinfunction "1_1") (pintype "passive"))
    )
    (net (code "37") (name "Net-(LED40-C)") (class "Default")
      (node (ref "LED40") (pin "K") (pinfunction "C_K") (pintype "passive"))
      (node (ref "LED41") (pin "K") (pinfunction "C_K") (pintype "passive"))
      (node (ref "LED42") (pin "K") (pinfunction "C_K") (pintype "passive"))
      (node (ref "LED43") (pin "K") (pinfunction "C_K") (pintype "passive"))
      (node (ref "R14") (pin "1") (pinfunction "1_1") (pintype "passive"))
    )
    (net (code "38") (name "Net-(LED47-C)") (class "Default")
      (node (ref "LED47") (pin "K") (pinfunction "C_K") (pintype "passive"))
      (node (ref "LED48") (pin "K") (pinfunction "C_K") (pintype "passive"))
      (node (ref "LED49") (pin "K") (pinfunction "C_K") (pintype "passive"))
      (node (ref "LED50") (pin "K") (pinfunction "C_K") (pintype "passive"))
      (node (ref "R16") (pin "1") (pinfunction "1_1") (pintype "passive"))
    )
    (net (code "39") (name "Net-(LED54-C)") (class "Default")
      (node (ref "LED54") (pin "K") (pinfunction "C_K") (pintype "passive"))
      (node (ref "LED55") (pin "K") (pinfunction "C_K") (pintype "passive"))
      (node (ref "LED56") (pin "K") (pinfunction "C_K") (pintype "passive"))
      (node (ref "LED57") (pin "K") (pinfunction "C_K") (pintype "passive"))
      (node (ref "R18") (pin "1") (pinfunction "1_1") (pintype "passive"))
    )
    (net (code "40") (name "Net-(LED61-C)") (class "Default")
      (node (ref "LED61") (pin "K") (pinfunction "C_K") (pintype "passive"))
      (node (ref "LED62") (pin "K") (pinfunction "C_K") (pintype "passive"))
      (node (ref "LED63") (pin "K") (pinfunction "C_K") (pintype "passive"))
      (node (ref "LED64") (pin "K") (pinfunction "C_K") (pintype "passive"))
      (node (ref "R20") (pin "1") (pinfunction "1_1") (pintype "passive"))
    )
    (net (code "41") (name "Net-(LED97-PadA)") (class "Default")
      (node (ref "LED97") (pin "A") (pinfunction "A_A") (pintype "passive"))
      (node (ref "R37") (pin "2") (pinfunction "2_2") (pintype "passive"))
    )
    (net (code "42") (name "Net-(LED98-PadA)") (class "Default")
      (node (ref "LED98") (pin "A") (pinfunction "A_A") (pintype "passive"))
      (node (ref "R38") (pin "2") (pinfunction "2_2") (pintype "passive"))
    )
    (net (code "43") (name "Net-(LED100-C)") (class "Default")
      (node (ref "LED100") (pin "K") (pinfunction "C_K") (pintype "passive"))
      (node (ref "LED117") (pin "K") (pinfunction "C_K") (pintype "passive"))
      (node (ref "LED118") (pin "K") (pinfunction "C_K") (pintype "passive"))
      (node (ref "LED119") (pin "K") (pinfunction "C_K") (pintype "passive"))
      (node (ref "R43") (pin "1") (pinfunction "1_1") (pintype "passive"))
    )
    (net (code "44") (name "Net-(LED101-C)") (class "Default")
      (node (ref "LED101") (pin "K") (pinfunction "C_K") (pintype "passive"))
      (node (ref "LED110") (pin "K") (pinfunction "C_K") (pintype "passive"))
      (node (ref "LED111") (pin "K") (pinfunction "C_K") (pintype "passive"))
      (node (ref "LED112") (pin "K") (pinfunction "C_K") (pintype "passive"))
      (node (ref "R41") (pin "1") (pinfunction "1_1") (pintype "passive"))
    )
    (net (code "45") (name "Net-(LED102-C)") (class "Default")
      (node (ref "LED102") (pin "K") (pinfunction "C_K") (pintype "passive"))
      (node (ref "LED124") (pin "K") (pinfunction "C_K") (pintype "passive"))
      (node (ref "LED125") (pin "K") (pinfunction "C_K") (pintype "passive"))
      (node (ref "LED126") (pin "K") (pinfunction "C_K") (pintype "passive"))
      (node (ref "R45") (pin "1") (pinfunction "1_1") (pintype "passive"))
    )
    (net (code "46") (name "Net-(LED103-C)") (class "Default")
      (node (ref "LED103") (pin "K") (pinfunction "C_K") (pintype "passive"))
      (node (ref "LED104") (pin "K") (pinfunction "C_K") (pintype "passive"))
      (node (ref "LED105") (pin "K") (pinfunction "C_K") (pintype "passive"))
      (node (ref "LED99") (pin "K") (pinfunction "C_K") (pintype "passive"))
      (node (ref "R39") (pin "1") (pinfunction "1_1") (pintype "passive"))
    )
    (net (code "47") (name "Net-(LED106-C)") (class "Default")
      (node (ref "LED106") (pin "K") (pinfunction "C_K") (pintype "passive"))
      (node (ref "LED107") (pin "K") (pinfunction "C_K") (pintype "passive"))
      (node (ref "LED108") (pin "K") (pinfunction "C_K") (pintype "passive"))
      (node (ref "LED109") (pin "K") (pinfunction "C_K") (pintype "passive"))
      (node (ref "R40") (pin "1") (pinfunction "1_1") (pintype "passive"))
    )
    (net (code "48") (name "Net-(LED113-C)") (class "Default")
      (node (ref "LED113") (pin "K") (pinfunction "C_K") (pintype "passive"))
      (node (ref "LED114") (pin "K") (pinfunction "C_K") (pintype "passive"))
      (node (ref "LED115") (pin "K") (pinfunction "C_K") (pintype "passive"))
      (node (ref "LED116") (pin "K") (pinfunction "C_K") (pintype "passive"))
      (node (ref "R42") (pin "1") (pinfunction "1_1") (pintype "passive"))
    )
    (net (code "49") (name "Net-(LED120-C)") (class "Default")
      (node (ref "LED120") (pin "K") (pinfunction "C_K") (pintype "passive"))
      (node (ref "LED121") (pin "K") (pinfunction "C_K") (pintype "passive"))
      (node (ref "LED122") (pin "K") (pinfunction "C_K") (pintype "passive"))
      (node (ref "LED123") (pin "K") (pinfunction "C_K") (pintype "passive"))
      (node (ref "R44") (pin "1") (pinfunction "1_1") (pintype "passive"))
    )
    (net (code "50") (name "Net-(LED127-C)") (class "Default")
      (node (ref "LED127") (pin "K") (pinfunction "C_K") (pintype "passive"))
      (node (ref "LED128") (pin "K") (pinfunction "C_K") (pintype "passive"))
      (node (ref "LED129") (pin "K") (pinfunction "C_K") (pintype "passive"))
      (node (ref "LED130") (pin "K") (pinfunction "C_K") (pintype "passive"))
      (node (ref "R46") (pin "1") (pinfunction "1_1") (pintype "passive"))
    )
    (net (code "51") (name "Net-(LED131-C)") (class "Default")
      (node (ref "LED131") (pin "K") (pinfunction "C_K") (pintype "passive"))
      (node (ref "LED135") (pin "K") (pinfunction "C_K") (pintype "passive"))
      (node (ref "LED136") (pin "K") (pinfunction "C_K") (pintype "passive"))
      (node (ref "LED137") (pin "K") (pinfunction "C_K") (pintype "passive"))
      (node (ref "R51") (pin "1") (pinfunction "1_1") (pintype "passive"))
    )
    (net (code "52") (name "Net-(LED132-C)") (class "Default")
      (node (ref "LED132") (pin "K") (pinfunction "C_K") (pintype "passive"))
      (node (ref "LED149") (pin "K") (pinfunction "C_K") (pintype "passive"))
      (node (ref "LED150") (pin "K") (pinfunction "C_K") (pintype "passive"))
      (node (ref "LED151") (pin "K") (pinfunction "C_K") (pintype "passive"))
      (node (ref "R55") (pin "1") (pinfunction "1_1") (pintype "passive"))
    )
    (net (code "53") (name "Net-(LED133-C)") (class "Default")
      (node (ref "LED133") (pin "K") (pinfunction "C_K") (pintype "passive"))
      (node (ref "LED142") (pin "K") (pinfunction "C_K") (pintype "passive"))
      (node (ref "LED143") (pin "K") (pinfunction "C_K") (pintype "passive"))
      (node (ref "LED144") (pin "K") (pinfunction "C_K") (pintype "passive"))
      (node (ref "R53") (pin "1") (pinfunction "1_1") (pintype "passive"))
    )
    (net (code "54") (name "Net-(LED134-C)") (class "Default")
      (node (ref "LED134") (pin "K") (pinfunction "C_K") (pintype "passive"))
      (node (ref "LED156") (pin "K") (pinfunction "C_K") (pintype "passive"))
      (node (ref "LED157") (pin "K") (pinfunction "C_K") (pintype "passive"))
      (node (ref "LED158") (pin "K") (pinfunction "C_K") (pintype "passive"))
      (node (ref "R57") (pin "1") (pinfunction "1_1") (pintype "passive"))
    )
    (net (code "55") (name "Net-(LED138-C)") (class "Default")
      (node (ref "LED138") (pin "K") (pinfunction "C_K") (pintype "passive"))
      (node (ref "LED139") (pin "K") (pinfunction "C_K") (pintype "passive"))
      (node (ref "LED140") (pin "K") (pinfunction "C_K") (pintype "passive"))
      (node (ref "LED141") (pin "K") (pinfunction "C_K") (pintype "passive"))
      (node (ref "R52") (pin "1") (pinfunction "1_1") (pintype "passive"))
    )
    (net (code "56") (name "Net-(LED145-C)") (class "Default")
      (node (ref "LED145") (pin "K") (pinfunction "C_K") (pintype "passive"))
      (node (ref "LED146") (pin "K") (pinfunction "C_K") (pintype "passive"))
      (node (ref "LED147") (pin "K") (pinfunction "C_K") (pintype "passive"))
      (node (ref "LED148") (pin "K") (pinfunction "C_K") (pintype "passive"))
      (node (ref "R54") (pin "1") (pinfunction "1_1") (pintype "passive"))
    )
    (net (code "57") (name "Net-(LED152-C)") (class "Default")
      (node (ref "LED152") (pin "K") (pinfunction "C_K") (pintype "passive"))
      (node (ref "LED153") (pin "K") (pinfunction "C_K") (pintype "passive"))
      (node (ref "LED154") (pin "K") (pinfunction "C_K") (pintype "passive"))
      (node (ref "LED155") (pin "K") (pinfunction "C_K") (pintype "passive"))
      (node (ref "R56") (pin "1") (pinfunction "1_1") (pintype "passive"))
    )
    (net (code "58") (name "Net-(LED159-C)") (class "Default")
      (node (ref "LED159") (pin "K") (pinfunction "C_K") (pintype "passive"))
      (node (ref "LED160") (pin "K") (pinfunction "C_K") (pintype "passive"))
      (node (ref "LED161") (pin "K") (pinfunction "C_K") (pintype "passive"))
      (node (ref "LED162") (pin "K") (pinfunction "C_K") (pintype "passive"))
      (node (ref "R58") (pin "1") (pinfunction "1_1") (pintype "passive"))
    )
    (net (code "59") (name "Net-(R21-Pad1)") (class "Default")
      (node (ref "R21") (pin "1") (pinfunction "1_1") (pintype "passive"))
      (node (ref "T5") (pin "B") (pinfunction "B_B") (pintype "passive"))
    )
    (net (code "60") (name "Net-(R22-Pad1)") (class "Default")
      (node (ref "R22") (pin "1") (pinfunction "1_1") (pintype "passive"))
      (node (ref "T6") (pin "B") (pinfunction "B_B") (pintype "passive"))
    )
    (net (code "61") (name "Net-(R23-Pad1)") (class "Default")
      (node (ref "R23") (pin "1") (pinfunction "1_1") (pintype "passive"))
      (node (ref "T7") (pin "B") (pinfunction "B_B") (pintype "passive"))
    )
    (net (code "62") (name "Net-(R24-Pad1)") (class "Default")
      (node (ref "R24") (pin "1") (pinfunction "1_1") (pintype "passive"))
      (node (ref "T8") (pin "B") (pinfunction "B_B") (pintype "passive"))
    )
    (net (code "63") (name "Net-(R47-Pad1)") (class "Default")
      (node (ref "R47") (pin "1") (pinfunction "1_1") (pintype "passive"))
      (node (ref "T13") (pin "B") (pinfunction "B_B") (pintype "passive"))
    )
    (net (code "64") (name "Net-(R48-Pad1)") (class "Default")
      (node (ref "R48") (pin "1") (pinfunction "1_1") (pintype "passive"))
      (node (ref "T14") (pin "B") (pinfunction "B_B") (pintype "passive"))
    )
    (net (code "65") (name "Net-(R49-Pad1)") (class "Default")
      (node (ref "R49") (pin "1") (pinfunction "1_1") (pintype "passive"))
      (node (ref "T15") (pin "B") (pinfunction "B_B") (pintype "passive"))
    )
    (net (code "66") (name "Net-(R50-Pad1)") (class "Default")
      (node (ref "R50") (pin "1") (pinfunction "1_1") (pintype "passive"))
      (node (ref "T16") (pin "B") (pinfunction "B_B") (pintype "passive"))
    )
    (net (code "67") (name "Net-(R59-Pad1)") (class "Default")
      (node (ref "R59") (pin "1") (pinfunction "1_1") (pintype "passive"))
      (node (ref "T17") (pin "B") (pinfunction "B_B") (pintype "passive"))
    )
    (net (code "68") (name "Net-(R60-Pad1)") (class "Default")
      (node (ref "R60") (pin "1") (pinfunction "1_1") (pintype "passive"))
      (node (ref "T18") (pin "B") (pinfunction "B_B") (pintype "passive"))
    )
    (net (code "69") (name "Net-(R61-Pad1)") (class "Default")
      (node (ref "R61") (pin "1") (pinfunction "1_1") (pintype "passive"))
      (node (ref "T19") (pin "B") (pinfunction "B_B") (pintype "passive"))
    )
    (net (code "70") (name "Net-(R62-Pad1)") (class "Default")
      (node (ref "R62") (pin "1") (pinfunction "1_1") (pintype "passive"))
      (node (ref "T20") (pin "B") (pinfunction "B_B") (pintype "passive"))
    )
    (net (code "71") (name "Net-(S1-P)") (class "Default")
      (node (ref "D1") (pin "C") (pinfunction "C_C") (pintype "passive"))
      (node (ref "S1") (pin "2") (pinfunction "P_2") (pintype "passive"))
    )
    (net (code "72") (name "POWEROFF") (class "Default")
      (node (ref "C3") (pin "2") (pinfunction "2_2") (pintype "passive"))
      (node (ref "R1") (pin "2") (pinfunction "2_2") (pintype "passive"))
      (node (ref "RPI") (pin "11") (pinfunction "GPIO17/GEN0_11") (pintype "bidirectional"))
      (node (ref "U$1") (pin "1") (pinfunction "P$1_1") (pintype "bidirectional"))
      (node (ref "U$1") (pin "2") (pinfunction "P$1_2") (pintype "bidirectional"))
    )
    (net (code "73") (name "RX") (class "Default")
      (node (ref "DEBUG_UART") (pin "4") (pinfunction "4_4") (pintype "passive"))
      (node (ref "RPI") (pin "10") (pinfunction "RXD0/GPIO15_10") (pintype "bidirectional"))
    )
    (net (code "74") (name "STATUS_LED") (class "Default")
      (node (ref "R38") (pin "1") (pinfunction "1_1") (pintype "passive"))
      (node (ref "RPI") (pin "35") (pinfunction "GPIO19_35") (pintype "bidirectional"))
    )
    (net (code "75") (name "TX") (class "Default")
      (node (ref "DEBUG_UART") (pin "5") (pinfunction "5_5") (pintype "passive"))
      (node (ref "RPI") (pin "8") (pinfunction "TXD0/GPIO14_8") (pintype "bidirectional"))
    )
    (net (code "76") (name "unconnected-(DEBUG_UART-Pad2)") (class "Default")
      (node (ref "DEBUG_UART") (pin "2") (pinfunction "2_2") (pintype "passive"))
    )
    (net (code "77") (name "unconnected-(DEBUG_UART-Pad3)") (class "Default")
      (node (ref "DEBUG_UART") (pin "3") (pinfunction "3_3") (pintype "passive"))
    )
    (net (code "78") (name "unconnected-(DEBUG_UART-Pad6)") (class "Default")
      (node (ref "DEBUG_UART") (pin "6") (pinfunction "6_6") (pintype "passive"))
    )
    (net (code "79") (name "unconnected-(RPI-GEN4{slash}GPIO23-Pad16)") (class "Default")
      (node (ref "RPI") (pin "16") (pinfunction "GEN4/GPIO23_16") (pintype "bidirectional"))
    )
    (net (code "80") (name "unconnected-(RPI-GEN5{slash}GPIO24-Pad18)") (class "Default")
      (node (ref "RPI") (pin "18") (pinfunction "GEN5/GPIO24_18") (pintype "bidirectional"))
    )
    (net (code "81") (name "unconnected-(RPI-GEN{slash}6GPIO25-Pad22)") (class "Default")
      (node (ref "RPI") (pin "22") (pinfunction "GEN/6GPIO25_22") (pintype "bidirectional"))
    )
    (net (code "82") (name "unconnected-(RPI-GPIO2{slash}SDA1-Pad3)") (class "Default")
      (node (ref "RPI") (pin "3") (pinfunction "GPIO2/SDA1_3") (pintype "bidirectional"))
    )
    (net (code "83") (name "unconnected-(RPI-GPIO3{slash}SCL1-Pad5)") (class "Default")
      (node (ref "RPI") (pin "5") (pinfunction "GPIO3/SCL1_5") (pintype "bidirectional"))
    )
    (net (code "84") (name "unconnected-(RPI-GPIO4{slash}GCKL-Pad7)") (class "Default")
      (node (ref "RPI") (pin "7") (pinfunction "GPIO4/GCKL_7") (pintype "bidirectional"))
    )
    (net (code "85") (name "unconnected-(RPI-GPIO12-Pad32)") (class "Default")
      (node (ref "RPI") (pin "32") (pinfunction "GPIO12_32") (pintype "bidirectional"))
    )
    (net (code "86") (name "unconnected-(RPI-GPIO18-Pad12)") (class "Default")
      (node (ref "RPI") (pin "12") (pinfunction "GPIO18_12") (pintype "bidirectional"))
    )
    (net (code "87") (name "unconnected-(RPI-ID_SC-Pad28)") (class "Default")
      (node (ref "RPI") (pin "28") (pinfunction "ID_SC_28") (pintype "bidirectional"))
    )
    (net (code "88") (name "unconnected-(RPI-ID_SD-Pad27)") (class "Default")
      (node (ref "RPI") (pin "27") (pinfunction "ID_SD_27") (pintype "bidirectional"))
    )
    (net (code "89") (name "unconnected-(RPI-~{CE0}{slash}GPIO8-Pad24)") (class "Default")
      (node (ref "RPI") (pin "24") (pinfunction "~{CE0}/GPIO8_24") (pintype "bidirectional"))
    )
    (net (code "90") (name "unconnected-(RPI-~{CE}{slash}GPIO7-Pad26)") (class "Default")
      (node (ref "RPI") (pin "26") (pinfunction "~{CE}/GPIO7_26") (pintype "bidirectional"))
    )
    (net (code "91") (name "unconnected-(S1-S-Pad3)") (class "Default")
      (node (ref "S1") (pin "3") (pinfunction "S_3") (pintype "passive"))
    )
  )
)
